# minDUINO_v1_6.net
KiCad netlist of a schematic drawn in EAGLE
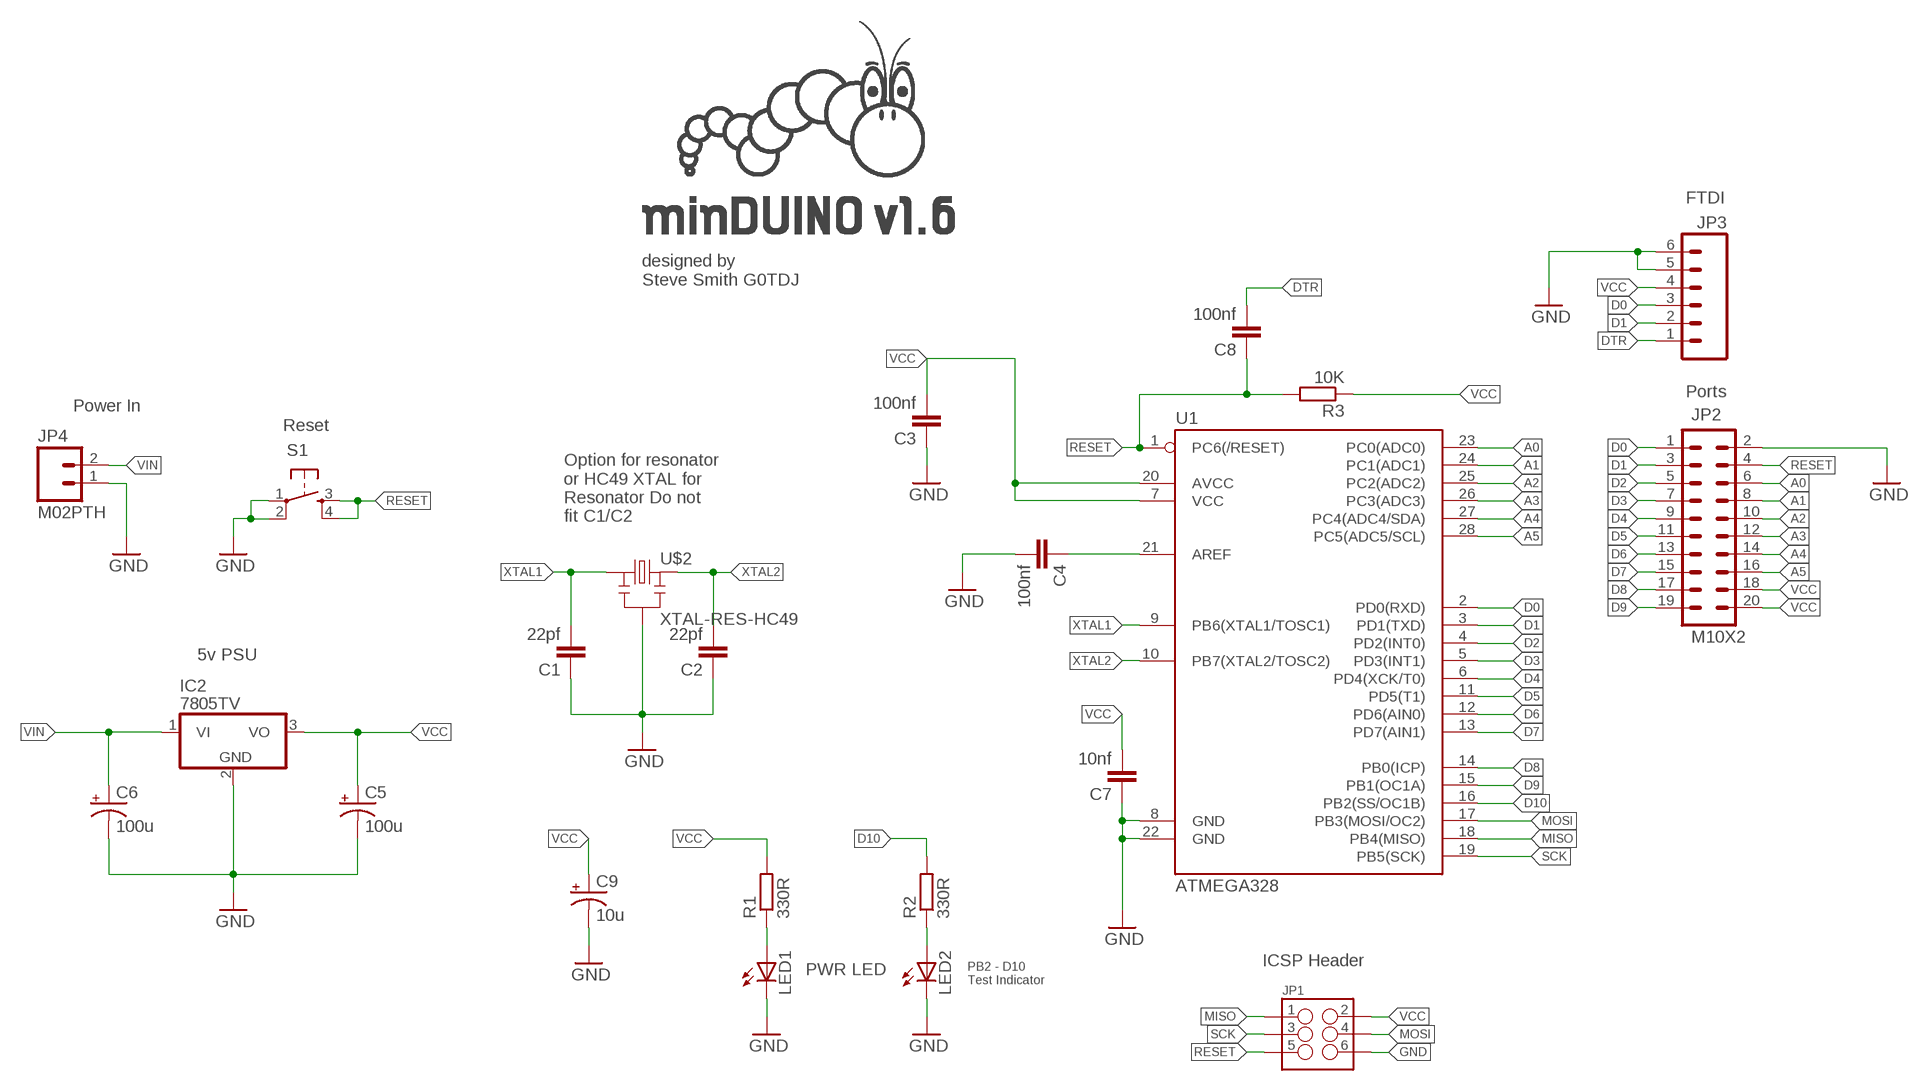
[diagram p0: schematic, sheet 1]

(export (version "E")
  (design (tool "Eeschema 10.0.6"))
  (components
    (comp (ref "C1")
      (value "22pf")
      (footprint "eagle-import:C050-030X075")
      (libsource (lib "eagle-import") (part "C-EU050-030X075"))
    )
    (comp (ref "C2")
      (value "22pf")
      (footprint "eagle-import:C050-030X075")
      (libsource (lib "eagle-import") (part "C-EU050-030X075"))
    )
    (comp (ref "C3")
      (value "100nf")
      (footprint "eagle-import:C050-030X075")
      (libsource (lib "eagle-import") (part "C-EU050-030X075"))
    )
    (comp (ref "C4")
      (value "100nf")
      (footprint "eagle-import:C050-030X075")
      (libsource (lib "eagle-import") (part "C-EU050-030X075"))
    )
    (comp (ref "C5")
      (value "100u")
      (footprint "eagle-import:CPOL-RADIAL-100UF-25V")
      (libsource (lib "eagle-import") (part "CAP_POLPTH1"))
    )
    (comp (ref "C6")
      (value "100u")
      (footprint "eagle-import:CPOL-RADIAL-100UF-25V")
      (libsource (lib "eagle-import") (part "CAP_POLPTH1"))
    )
    (comp (ref "C7")
      (value "10nf")
      (footprint "eagle-import:C050-030X075")
      (libsource (lib "eagle-import") (part "C-EU050-030X075"))
    )
    (comp (ref "C8")
      (value "100nf")
      (footprint "eagle-import:C050-030X075")
      (libsource (lib "eagle-import") (part "C-EU050-030X075"))
    )
    (comp (ref "C9")
      (value "10u")
      (footprint "eagle-import:CPOL-RADIAL-100UF-25V")
      (libsource (lib "eagle-import") (part "CAP_POLPTH1"))
    )
    (comp (ref "IC2")
      (value "7805TV")
      (footprint "eagle-import:TO220V")
      (libsource (lib "eagle-import") (part "78TV05"))
    )
    (comp (ref "JP1")
      (value "M03X2SHROUD")
      (footprint "eagle-import:2X3-SHROUDED")
      (libsource (lib "eagle-import") (part "M03X2SHROUD"))
    )
    (comp (ref "JP2")
      (value "M10X2")
      (footprint "eagle-import:2X10")
      (libsource (lib "eagle-import") (part "M10X2"))
    )
    (comp (ref "JP3")
      (value "M06SIP")
      (footprint "eagle-import:1X06")
      (libsource (lib "eagle-import") (part "M06SIP"))
    )
    (comp (ref "JP4")
      (value "M02PTH")
      (footprint "eagle-import:1X02")
      (libsource (lib "eagle-import") (part "M02PTH"))
    )
    (comp (ref "LED1")
      (value "LED3MM")
      (footprint "eagle-import:LED3MM")
      (libsource (lib "eagle-import") (part "LED3MM"))
    )
    (comp (ref "LED2")
      (value "LED3MM")
      (footprint "eagle-import:LED3MM")
      (libsource (lib "eagle-import") (part "LED3MM"))
    )
    (comp (ref "R1")
      (value "330R")
      (footprint "eagle-import:0411V")
      (libsource (lib "eagle-import") (part "R-EU_0411/3V"))
    )
    (comp (ref "R2")
      (value "330R")
      (footprint "eagle-import:0411V")
      (libsource (lib "eagle-import") (part "R-EU_0411/3V"))
    )
    (comp (ref "R3")
      (value "10K")
      (footprint "eagle-import:0411V")
      (libsource (lib "eagle-import") (part "R-EU_0411/3V"))
    )
    (comp (ref "S1")
      (value "TAC_SWITCHPTH")
      (footprint "eagle-import:TACTILE-PTH")
      (libsource (lib "eagle-import") (part "TAC_SWITCHPTH"))
    )
    (comp (ref "U$1")
      (value "MINDUINO_WORDMARK_V1.6")
      (footprint "eagle-import:MINDUINO_WORDMARK_V1.6")
      (libsource (lib "eagle-import") (part "MINDUINO_WORDMARK_V1.6"))
    )
    (comp (ref "U$2")
      (value "XTAL-RES-HC49")
      (footprint "eagle-import:XTAL-RES-HC49")
      (libsource (lib "eagle-import") (part "XTAL-RES-HC49"))
    )
    (comp (ref "U$4")
      (value "MINDUINO_CATERPILLAR")
      (footprint "eagle-import:MINDUINO_CATERPILLAR")
      (libsource (lib "eagle-import") (part "MINDUINO_CATERPILLAR"))
    )
    (comp (ref "U1")
      (value "ATMEGA328")
      (footprint "eagle-import:DIL28-3")
      (libsource (lib "eagle-import") (part "ATMEGA328"))
    )
  )
  (nets
    (net (code "1") (name "A0") (class "Default")
      (node (ref "JP2") (pin "6") (pinfunction "6_6") (pintype "passive"))
      (node (ref "U1") (pin "23") (pinfunction "PC0(ADC0)_23") (pintype "bidirectional"))
    )
    (net (code "2") (name "A1") (class "Default")
      (node (ref "JP2") (pin "8") (pinfunction "8_8") (pintype "passive"))
      (node (ref "U1") (pin "24") (pinfunction "PC1(ADC1)_24") (pintype "bidirectional"))
    )
    (net (code "3") (name "A2") (class "Default")
      (node (ref "JP2") (pin "10") (pinfunction "10_10") (pintype "passive"))
      (node (ref "U1") (pin "25") (pinfunction "PC2(ADC2)_25") (pintype "bidirectional"))
    )
    (net (code "4") (name "A3") (class "Default")
      (node (ref "JP2") (pin "12") (pinfunction "12_12") (pintype "passive"))
      (node (ref "U1") (pin "26") (pinfunction "PC3(ADC3)_26") (pintype "bidirectional"))
    )
    (net (code "5") (name "A4") (class "Default")
      (node (ref "JP2") (pin "14") (pinfunction "14_14") (pintype "passive"))
      (node (ref "U1") (pin "27") (pinfunction "PC4(ADC4/SDA)_27") (pintype "bidirectional"))
    )
    (net (code "6") (name "A5") (class "Default")
      (node (ref "JP2") (pin "16") (pinfunction "16_16") (pintype "passive"))
      (node (ref "U1") (pin "28") (pinfunction "PC5(ADC5/SCL)_28") (pintype "bidirectional"))
    )
    (net (code "7") (name "D0") (class "Default")
      (node (ref "JP2") (pin "1") (pinfunction "1_1") (pintype "passive"))
      (node (ref "JP3") (pin "3") (pinfunction "3_3") (pintype "passive"))
      (node (ref "U1") (pin "2") (pinfunction "PD0(RXD)_2") (pintype "bidirectional"))
    )
    (net (code "8") (name "D1") (class "Default")
      (node (ref "JP2") (pin "3") (pinfunction "3_3") (pintype "passive"))
      (node (ref "JP3") (pin "2") (pinfunction "2_2") (pintype "passive"))
      (node (ref "U1") (pin "3") (pinfunction "PD1(TXD)_3") (pintype "bidirectional"))
    )
    (net (code "9") (name "D2") (class "Default")
      (node (ref "JP2") (pin "5") (pinfunction "5_5") (pintype "passive"))
      (node (ref "U1") (pin "4") (pinfunction "PD2(INT0)_4") (pintype "bidirectional"))
    )
    (net (code "10") (name "D3") (class "Default")
      (node (ref "JP2") (pin "7") (pinfunction "7_7") (pintype "passive"))
      (node (ref "U1") (pin "5") (pinfunction "PD3(INT1)_5") (pintype "bidirectional"))
    )
    (net (code "11") (name "D4") (class "Default")
      (node (ref "JP2") (pin "9") (pinfunction "9_9") (pintype "passive"))
      (node (ref "U1") (pin "6") (pinfunction "PD4(XCK/T0)_6") (pintype "bidirectional"))
    )
    (net (code "12") (name "D5") (class "Default")
      (node (ref "JP2") (pin "11") (pinfunction "11_11") (pintype "passive"))
      (node (ref "U1") (pin "11") (pinfunction "PD5(T1)_11") (pintype "bidirectional"))
    )
    (net (code "13") (name "D6") (class "Default")
      (node (ref "JP2") (pin "13") (pinfunction "13_13") (pintype "passive"))
      (node (ref "U1") (pin "12") (pinfunction "PD6(AIN0)_12") (pintype "bidirectional"))
    )
    (net (code "14") (name "D7") (class "Default")
      (node (ref "JP2") (pin "15") (pinfunction "15_15") (pintype "passive"))
      (node (ref "U1") (pin "13") (pinfunction "PD7(AIN1)_13") (pintype "bidirectional"))
    )
    (net (code "15") (name "D8") (class "Default")
      (node (ref "JP2") (pin "17") (pinfunction "17_17") (pintype "passive"))
      (node (ref "U1") (pin "14") (pinfunction "PB0(ICP)_14") (pintype "bidirectional"))
    )
    (net (code "16") (name "D9") (class "Default")
      (node (ref "JP2") (pin "19") (pinfunction "19_19") (pintype "passive"))
      (node (ref "U1") (pin "15") (pinfunction "PB1(OC1A)_15") (pintype "bidirectional"))
    )
    (net (code "17") (name "D10") (class "Default")
      (node (ref "R2") (pin "2") (pinfunction "2_2") (pintype "passive"))
      (node (ref "U1") (pin "16") (pinfunction "PB2(SS/OC1B)_16") (pintype "bidirectional"))
    )
    (net (code "18") (name "DTR") (class "Default")
      (node (ref "C8") (pin "2") (pinfunction "2_2") (pintype "passive"))
      (node (ref "JP3") (pin "1") (pinfunction "1_1") (pintype "passive"))
    )
    (net (code "19") (name "GND") (class "Default")
      (node (ref "C1") (pin "1") (pinfunction "1_1") (pintype "passive"))
      (node (ref "C2") (pin "1") (pinfunction "1_1") (pintype "passive"))
      (node (ref "C3") (pin "1") (pinfunction "1_1") (pintype "passive"))
      (node (ref "C4") (pin "2") (pinfunction "2_2") (pintype "passive"))
      (node (ref "C5") (pin "2") (pinfunction "-_2") (pintype "passive"))
      (node (ref "C6") (pin "2") (pinfunction "-_2") (pintype "passive"))
      (node (ref "C7") (pin "1") (pinfunction "1_1") (pintype "passive"))
      (node (ref "C9") (pin "2") (pinfunction "-_2") (pintype "passive"))
      (node (ref "IC2") (pin "2") (pinfunction "GND_2") (pintype "passive"))
      (node (ref "JP1") (pin "6") (pinfunction "6_6") (pintype "bidirectional"))
      (node (ref "JP2") (pin "2") (pinfunction "2_2") (pintype "passive"))
      (node (ref "JP3") (pin "5") (pinfunction "5_5") (pintype "passive"))
      (node (ref "JP3") (pin "6") (pinfunction "6_6") (pintype "passive"))
      (node (ref "JP4") (pin "1") (pinfunction "1_1") (pintype "passive"))
      (node (ref "LED1") (pin "K") (pinfunction "C_K") (pintype "passive"))
      (node (ref "LED2") (pin "K") (pinfunction "C_K") (pintype "passive"))
      (node (ref "S1") (pin "1") (pinfunction "1_1") (pintype "passive"))
      (node (ref "S1") (pin "2") (pinfunction "2_2") (pintype "passive"))
      (node (ref "U$2") (pin "2") (pinfunction "2_2") (pintype "passive"))
      (node (ref "U1") (pin "22") (pinfunction "GND_22") (pintype "bidirectional"))
      (node (ref "U1") (pin "8") (pinfunction "GND_8") (pintype "bidirectional"))
    )
    (net (code "20") (name "MISO") (class "Default")
      (node (ref "JP1") (pin "1") (pinfunction "1_1") (pintype "bidirectional"))
      (node (ref "U1") (pin "18") (pinfunction "PB4(MISO)_18") (pintype "bidirectional"))
    )
    (net (code "21") (name "MOSI") (class "Default")
      (node (ref "JP1") (pin "4") (pinfunction "4_4") (pintype "bidirectional"))
      (node (ref "U1") (pin "17") (pinfunction "PB3(MOSI/OC2)_17") (pintype "bidirectional"))
    )
    (net (code "22") (name "Net-(LED1-PadA)") (class "Default")
      (node (ref "LED1") (pin "A") (pinfunction "A_A") (pintype "passive"))
      (node (ref "R1") (pin "1") (pinfunction "1_1") (pintype "passive"))
    )
    (net (code "23") (name "Net-(LED2-PadA)") (class "Default")
      (node (ref "LED2") (pin "A") (pinfunction "A_A") (pintype "passive"))
      (node (ref "R2") (pin "1") (pinfunction "1_1") (pintype "passive"))
    )
    (net (code "24") (name "Net-(U1-AREF)") (class "Default")
      (node (ref "C4") (pin "1") (pinfunction "1_1") (pintype "passive"))
      (node (ref "U1") (pin "21") (pinfunction "AREF_21") (pintype "bidirectional"))
    )
    (net (code "25") (name "RESET") (class "Default")
      (node (ref "C8") (pin "1") (pinfunction "1_1") (pintype "passive"))
      (node (ref "JP1") (pin "5") (pinfunction "5_5") (pintype "bidirectional"))
      (node (ref "JP2") (pin "4") (pinfunction "4_4") (pintype "passive"))
      (node (ref "R3") (pin "2") (pinfunction "2_2") (pintype "passive"))
      (node (ref "S1") (pin "3") (pinfunction "3_3") (pintype "passive"))
      (node (ref "S1") (pin "4") (pinfunction "4_4") (pintype "passive"))
      (node (ref "U1") (pin "1") (pinfunction "PC6(/RESET)_1") (pintype "bidirectional"))
    )
    (net (code "26") (name "SCK") (class "Default")
      (node (ref "JP1") (pin "3") (pinfunction "3_3") (pintype "bidirectional"))
      (node (ref "U1") (pin "19") (pinfunction "PB5(SCK)_19") (pintype "bidirectional"))
    )
    (net (code "27") (name "VCC") (class "Default")
      (node (ref "C3") (pin "2") (pinfunction "2_2") (pintype "passive"))
      (node (ref "C5") (pin "1") (pinfunction "+_1") (pintype "passive"))
      (node (ref "C7") (pin "2") (pinfunction "2_2") (pintype "passive"))
      (node (ref "C9") (pin "1") (pinfunction "+_1") (pintype "passive"))
      (node (ref "IC2") (pin "3") (pinfunction "VO_3") (pintype "passive"))
      (node (ref "JP1") (pin "2") (pinfunction "2_2") (pintype "bidirectional"))
      (node (ref "JP2") (pin "18") (pinfunction "18_18") (pintype "passive"))
      (node (ref "JP2") (pin "20") (pinfunction "20_20") (pintype "passive"))
      (node (ref "JP3") (pin "4") (pinfunction "4_4") (pintype "passive"))
      (node (ref "R1") (pin "2") (pinfunction "2_2") (pintype "passive"))
      (node (ref "R3") (pin "1") (pinfunction "1_1") (pintype "passive"))
      (node (ref "U1") (pin "20") (pinfunction "AVCC_20") (pintype "bidirectional"))
      (node (ref "U1") (pin "7") (pinfunction "VCC_7") (pintype "bidirectional"))
    )
    (net (code "28") (name "VIN") (class "Default")
      (node (ref "C6") (pin "1") (pinfunction "+_1") (pintype "passive"))
      (node (ref "IC2") (pin "1") (pinfunction "VI_1") (pintype "input"))
      (node (ref "JP4") (pin "2") (pinfunction "2_2") (pintype "passive"))
    )
    (net (code "29") (name "XTAL1") (class "Default")
      (node (ref "C1") (pin "2") (pinfunction "2_2") (pintype "passive"))
      (node (ref "U$2") (pin "1") (pinfunction "1_1") (pintype "passive"))
      (node (ref "U1") (pin "9") (pinfunction "PB6(XTAL1/TOSC1)_9") (pintype "bidirectional"))
    )
    (net (code "30") (name "XTAL2") (class "Default")
      (node (ref "C2") (pin "2") (pinfunction "2_2") (pintype "passive"))
      (node (ref "U$2") (pin "3") (pinfunction "3_3") (pintype "passive"))
      (node (ref "U1") (pin "10") (pinfunction "PB7(XTAL2/TOSC2)_10") (pintype "bidirectional"))
    )
  )
)
